# KMO_IO_MV2_7.net
KiCad netlist of a schematic drawn in EAGLE
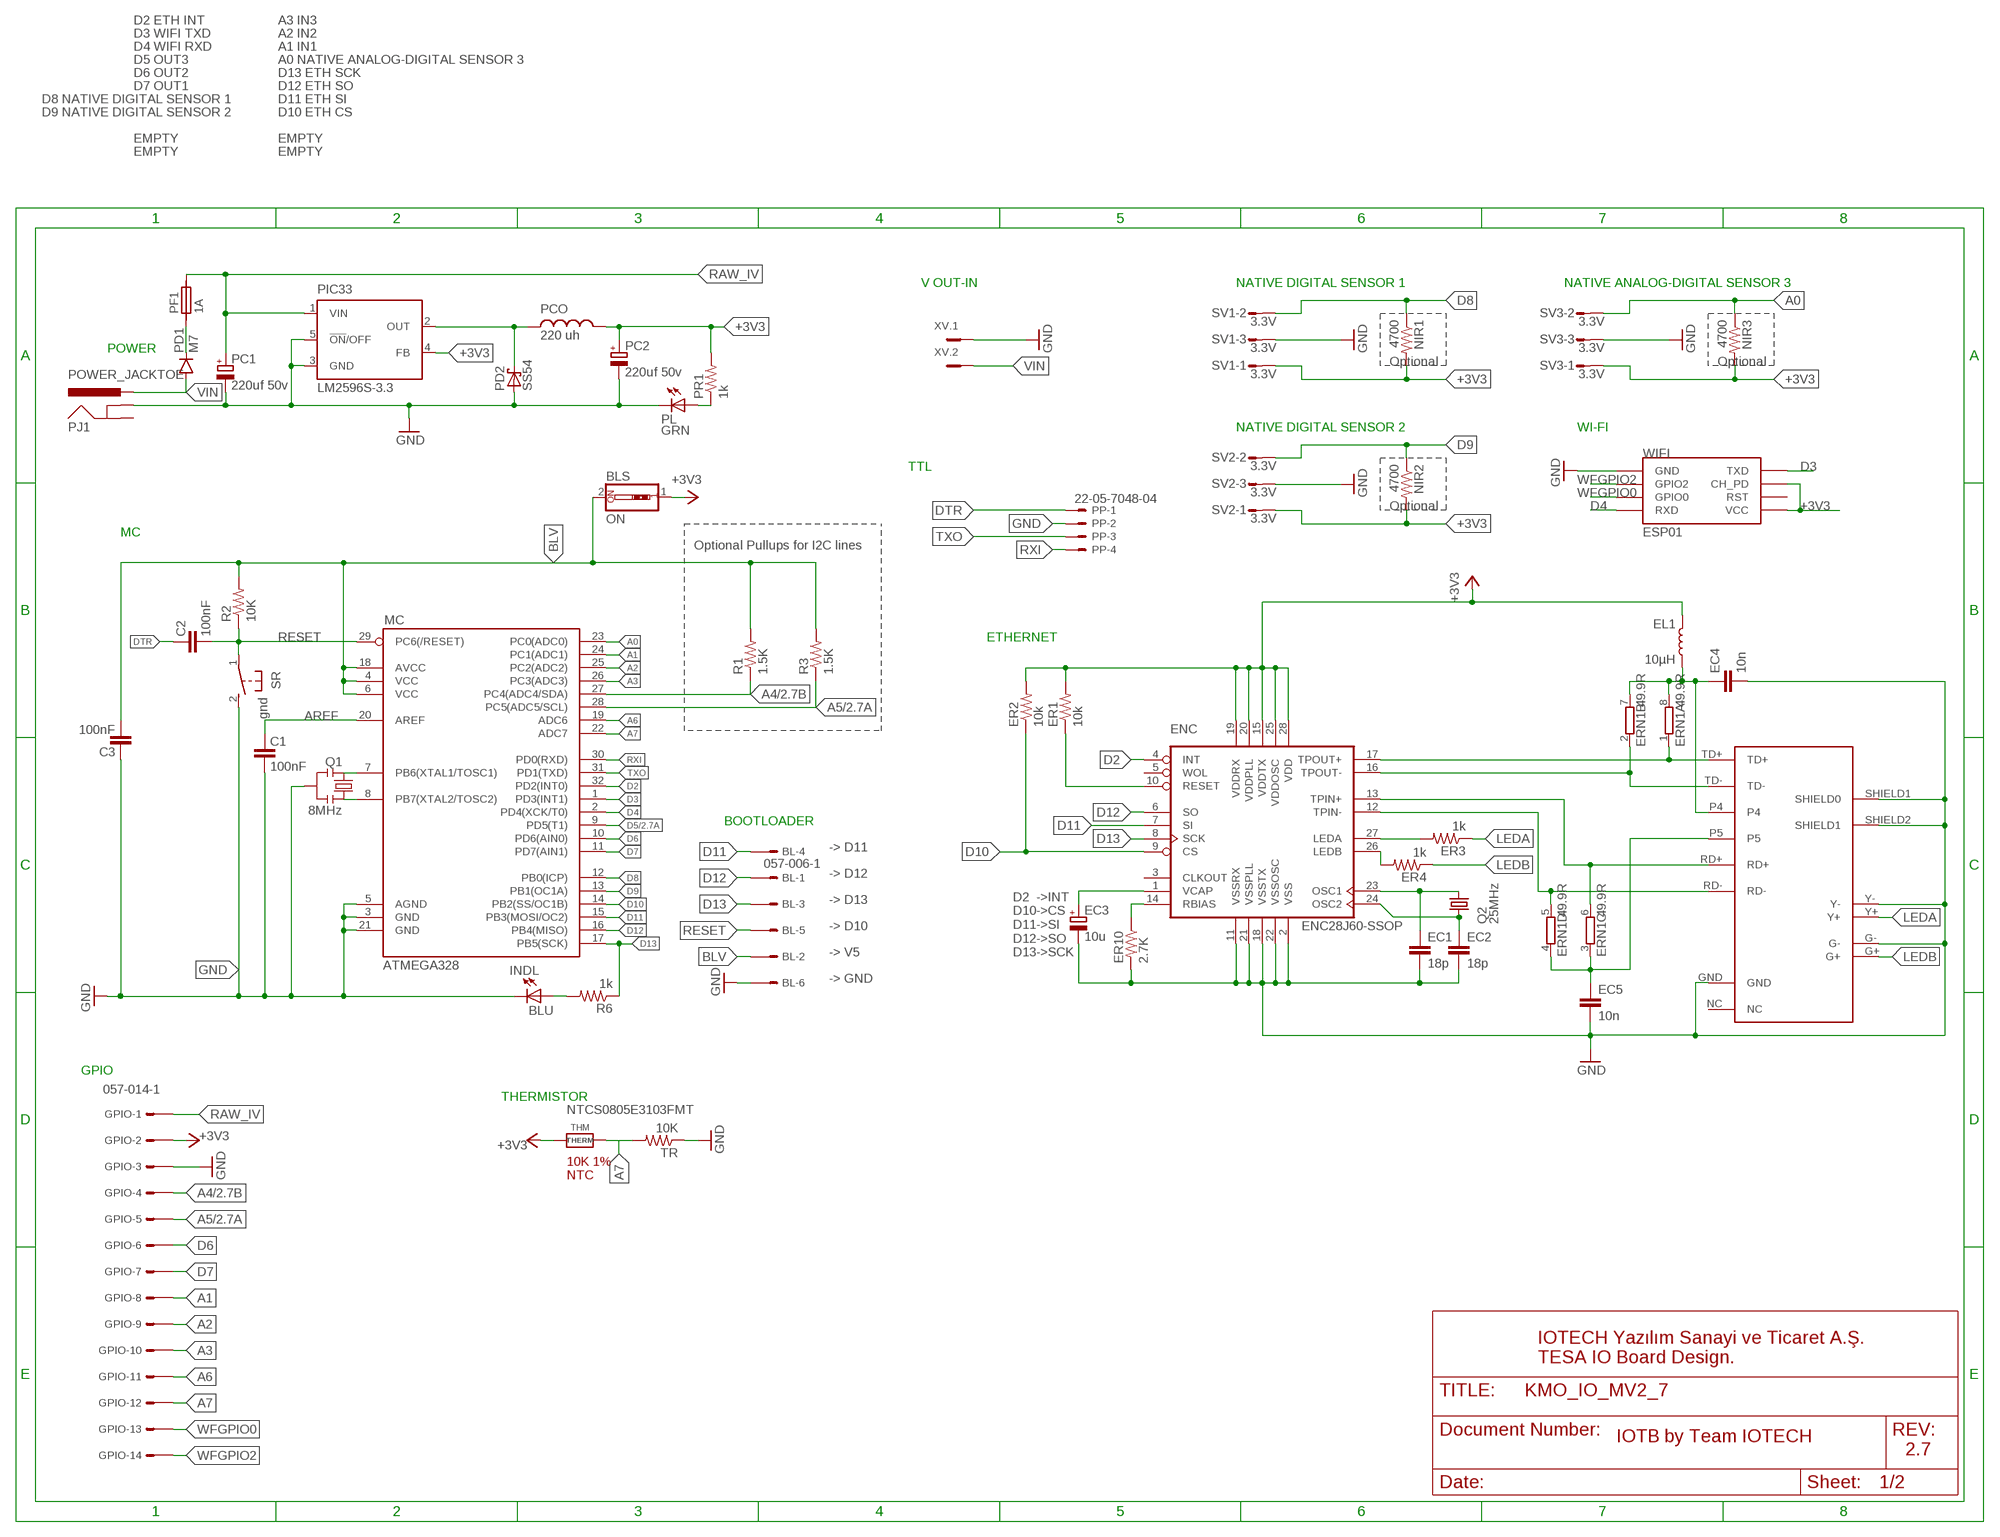
[diagram p0: schematic, sheet 1]
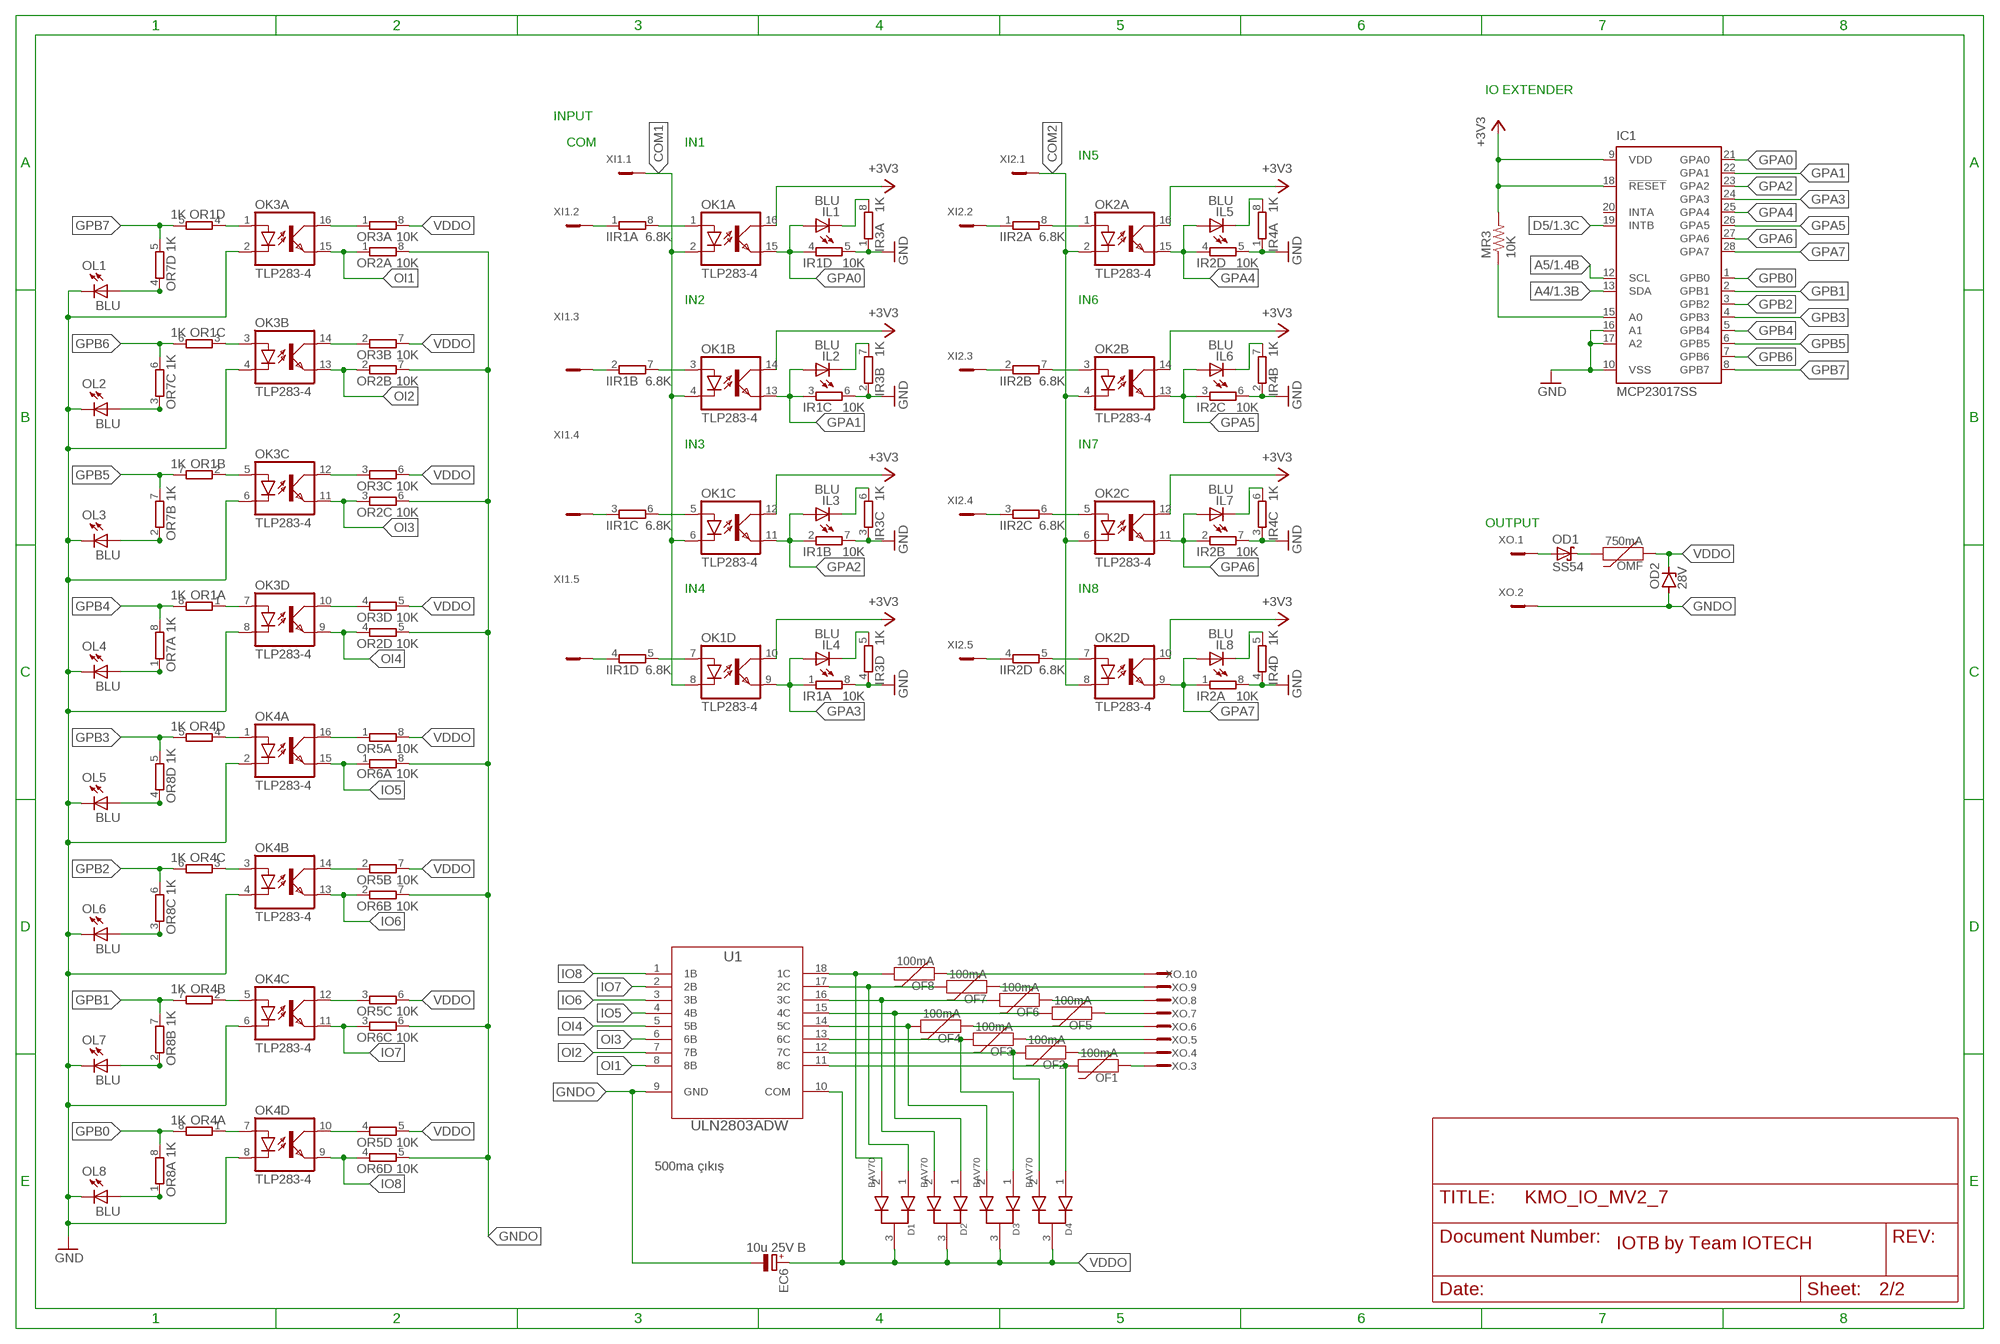
[diagram p1: schematic, sheet 2]

(export (version "E")
  (design (tool "Eeschema 10.0.6"))
  (components
    (comp (ref "BL")
      (value "057-006-1")
      (footprint "eagle-import:057-006-1")
      (libsource (lib "eagle-import") (part "057-006-1"))
    )
    (comp (ref "BLS")
      (value "ON")
      (footprint "eagle-import:EDG-01")
      (libsource (lib "eagle-import") (part "SW_DIP-1"))
    )
    (comp (ref "C1")
      (value "100nF")
      (footprint "eagle-import:0805")
      (libsource (lib "eagle-import") (part "CAP0805"))
    )
    (comp (ref "C2")
      (value "100nF")
      (footprint "eagle-import:0805")
      (libsource (lib "eagle-import") (part "CAP0805"))
    )
    (comp (ref "C3")
      (value "100nF")
      (footprint "eagle-import:0805")
      (libsource (lib "eagle-import") (part "CAP0805"))
    )
    (comp (ref "EC1")
      (value "18p")
      (footprint "eagle-import:0805")
      (libsource (lib "eagle-import") (part "CAP0805"))
    )
    (comp (ref "EC2")
      (value "18p")
      (footprint "eagle-import:0805")
      (libsource (lib "eagle-import") (part "CAP0805"))
    )
    (comp (ref "EC3")
      (value "10u")
      (footprint "eagle-import:CT3216")
      (libsource (lib "eagle-import") (part "CPOL-EUCT3216"))
    )
    (comp (ref "EC4")
      (value "10n")
      (footprint "eagle-import:0805")
      (libsource (lib "eagle-import") (part "CAP0805"))
    )
    (comp (ref "EC5")
      (value "10n")
      (footprint "eagle-import:0805")
      (libsource (lib "eagle-import") (part "CAP0805"))
    )
    (comp (ref "EL1")
      (value "10µH")
      (footprint "eagle-import:0805")
      (libsource (lib "eagle-import") (part "INDUCTOR-0805-3.3UH"))
    )
    (comp (ref "ENC")
      (value "ENC28J60-SSOP")
      (footprint "eagle-import:SSOP28")
      (libsource (lib "eagle-import") (part "ENC28J60-SSOP"))
    )
    (comp (ref "ER1")
      (value "10k")
      (footprint "eagle-import:0805")
      (libsource (lib "eagle-import") (part "RESISTOR0805-RES"))
    )
    (comp (ref "ER2")
      (value "10k")
      (footprint "eagle-import:0805")
      (libsource (lib "eagle-import") (part "RESISTOR0805-RES"))
    )
    (comp (ref "ER3")
      (value "1k")
      (footprint "eagle-import:0805")
      (libsource (lib "eagle-import") (part "RESISTOR0805-RES"))
    )
    (comp (ref "ER4")
      (value "1k")
      (footprint "eagle-import:0805")
      (libsource (lib "eagle-import") (part "RESISTOR0805-RES"))
    )
    (comp (ref "ER10")
      (value "2.7K")
      (footprint "eagle-import:0805")
      (libsource (lib "eagle-import") (part "RESISTOR0805-RES"))
    )
    (comp (ref "ERN1")
      (value "49.9R")
      (footprint "eagle-import:0603-ARV")
      (libsource (lib "eagle-import") (part "4R-N0603-ARV"))
    )
    (comp (ref "GPIO")
      (value "057-014-1")
      (footprint "eagle-import:057-014-1")
      (libsource (lib "eagle-import") (part "057-014-1"))
    )
    (comp (ref "INDL")
      (value "BLU")
      (footprint "eagle-import:CHIP-LED0805")
      (libsource (lib "eagle-import") (part "LEDCHIP-LED0805"))
    )
    (comp (ref "MC")
      (value "ATMEGA328")
      (footprint "eagle-import:TQFP32-08")
      (libsource (lib "eagle-import") (part "ATMEGA168"))
    )
    (comp (ref "NIR1")
      (value "4700")
      (footprint "eagle-import:0805")
      (libsource (lib "eagle-import") (part "RESISTOR0805-RES"))
    )
    (comp (ref "NIR2")
      (value "4700")
      (footprint "eagle-import:0805")
      (libsource (lib "eagle-import") (part "RESISTOR0805-RES"))
    )
    (comp (ref "NIR3")
      (value "4700")
      (footprint "eagle-import:0805")
      (libsource (lib "eagle-import") (part "RESISTOR0805-RES"))
    )
    (comp (ref "PC1")
      (value "220uf 50v")
      (footprint "eagle-import:140CLH-1010")
      (libsource (lib "eagle-import") (part "CPOL-EU140CLH-1010"))
    )
    (comp (ref "PC2")
      (value "220uf 50v")
      (footprint "eagle-import:140CLH-1010")
      (libsource (lib "eagle-import") (part "CPOL-EU140CLH-1010"))
    )
    (comp (ref "PCO")
      (value "220 uh")
      (footprint "eagle-import:MSS1260")
      (libsource (lib "eagle-import") (part "MSS1260"))
    )
    (comp (ref "PD1")
      (value "M7")
      (footprint "eagle-import:SMA-DIODE")
      (libsource (lib "eagle-import") (part "DIODESMA"))
    )
    (comp (ref "PD2")
      (value "SS54")
      (footprint "eagle-import:SMB")
      (libsource (lib "eagle-import") (part "SCHOTTKY-DIODESMD"))
    )
    (comp (ref "PF1")
      (value "1A")
      (footprint "eagle-import:1820")
      (libsource (lib "eagle-import") (part "SIBA194600"))
    )
    (comp (ref "PIC33")
      (value "LM2596S-3.3")
      (footprint "eagle-import:TO263-5")
      (fields
        (field (name "MF") "NATIONAL SEMICONDUCTOR")
        (field (name "MPN") "LM2596S-ADJ/NOPB")
        (field (name "SPICEPREFIX") "X")
      )
      (libsource (lib "eagle-import") (part "LM2596S"))
    )
    (comp (ref "PJ1")
      (value "POWER_JACKTOE")
      (footprint "eagle-import:POWER_JACK_SMD_OVERPASTE_TOE")
      (libsource (lib "eagle-import") (part "POWER_JACKTOE"))
    )
    (comp (ref "PL")
      (value "GRN")
      (footprint "eagle-import:CHIP-LED0805")
      (libsource (lib "eagle-import") (part "LEDCHIP-LED0805"))
    )
    (comp (ref "PP")
      (value "22-05-7048-04")
      (footprint "eagle-import:7395-04")
      (fields (field (name "MF") "MOLEX"))
      (libsource (lib "eagle-import") (part "22-?-0405-7048"))
    )
    (comp (ref "PR1")
      (value "1k")
      (footprint "eagle-import:0805")
      (libsource (lib "eagle-import") (part "RESISTOR0805-RES"))
    )
    (comp (ref "Q1")
      (value "8MHz")
      (footprint "eagle-import:RESONATOR-SMD-1_1")
      (libsource (lib "eagle-import") (part "RESONATOR1{colon}1"))
    )
    (comp (ref "Q2")
      (value "25MHz")
      (footprint "eagle-import:5.0X3.2_2")
      (libsource (lib "eagle-import") (part "KX-9B"))
    )
    (comp (ref "R1")
      (value "1.5K")
      (footprint "eagle-import:0805")
      (libsource (lib "eagle-import") (part "RESISTOR0805-RES"))
    )
    (comp (ref "R2")
      (value "10K")
      (footprint "eagle-import:0805")
      (libsource (lib "eagle-import") (part "RESISTOR0805-RES"))
    )
    (comp (ref "R3")
      (value "1.5K")
      (footprint "eagle-import:0805")
      (libsource (lib "eagle-import") (part "RESISTOR0805-RES"))
    )
    (comp (ref "R6")
      (value "1k")
      (footprint "eagle-import:0805")
      (libsource (lib "eagle-import") (part "RESISTOR0805-RES"))
    )
    (comp (ref "SR")
      (value "gnd")
      (footprint "eagle-import:B3F-31XX")
      (fields (field (name "MPN") "B3F-3100"))
      (libsource (lib "eagle-import") (part "31-XX"))
    )
    (comp (ref "SV1")
      (value "3.3V")
      (footprint "eagle-import:S03P")
      (libsource (lib "eagle-import") (part "S03P"))
    )
    (comp (ref "SV2")
      (value "3.3V")
      (footprint "eagle-import:S03P")
      (libsource (lib "eagle-import") (part "S03P"))
    )
    (comp (ref "SV3")
      (value "3.3V")
      (footprint "eagle-import:S03P")
      (libsource (lib "eagle-import") (part "S03P"))
    )
    (comp (ref "THM")
      (value "THERM")
      (footprint "eagle-import:MICROBUILDER_0805_NOTHERMALS")
      (libsource (lib "eagle-import") (part "MICROBUILDER_RESISTOR0805_NOTHERMALS"))
    )
    (comp (ref "TR")
      (value "10K")
      (footprint "eagle-import:0805")
      (libsource (lib "eagle-import") (part "RESISTOR0805-RES"))
    )
    (comp (ref "U$2")
      (value "HR911105A")
      (footprint "eagle-import:RJ45")
      (libsource (lib "eagle-import") (part "HR911105A"))
    )
    (comp (ref "WIFI")
      (value "ESP01")
      (footprint "eagle-import:ESP01")
      (libsource (lib "eagle-import") (part "ESP01"))
    )
    (comp (ref "XV")
      (value "MC2")
      (footprint "eagle-import:MC2")
      (libsource (lib "eagle-import") (part "MC2"))
    )
    (comp (ref "D1")
      (value "BAV70")
      (footprint "eagle-import:SOT-23-3")
      (fields (field (name "MF") "Multicomp") (field (name "MP") "BAV70+"))
      (libsource (lib "eagle-import") (part "BAV70"))
    )
    (comp (ref "D2")
      (value "BAV70")
      (footprint "eagle-import:SOT-23-3")
      (fields (field (name "MF") "Multicomp") (field (name "MP") "BAV70+"))
      (libsource (lib "eagle-import") (part "BAV70"))
    )
    (comp (ref "D3")
      (value "BAV70")
      (footprint "eagle-import:SOT-23-3")
      (fields (field (name "MF") "Multicomp") (field (name "MP") "BAV70+"))
      (libsource (lib "eagle-import") (part "BAV70"))
    )
    (comp (ref "D4")
      (value "BAV70")
      (footprint "eagle-import:SOT-23-3")
      (fields (field (name "MF") "Multicomp") (field (name "MP") "BAV70+"))
      (libsource (lib "eagle-import") (part "BAV70"))
    )
    (comp (ref "EC6")
      (value "10u 25V B")
      (footprint "eagle-import:SMC_B")
      (libsource (lib "eagle-import") (part "CPOL-EUSMCB"))
    )
    (comp (ref "IC1")
      (value "MCP23017SS")
      (footprint "eagle-import:SSOP28")
      (fields (field (name "MF") "MICROCHIP") (field (name "MPN") "MCP23017-E/SS"))
      (libsource (lib "eagle-import") (part "MCP23017SS"))
    )
    (comp (ref "IIR1")
      (value "6.8K")
      (footprint "eagle-import:0603-ARV")
      (libsource (lib "eagle-import") (part "4R-N0603-ARV"))
    )
    (comp (ref "IIR2")
      (value "6.8K")
      (footprint "eagle-import:0603-ARV")
      (libsource (lib "eagle-import") (part "4R-N0603-ARV"))
    )
    (comp (ref "IL1")
      (value "BLU")
      (footprint "eagle-import:CHIP-LED0805")
      (libsource (lib "eagle-import") (part "LEDCHIP-LED0805"))
    )
    (comp (ref "IL2")
      (value "BLU")
      (footprint "eagle-import:CHIP-LED0805")
      (libsource (lib "eagle-import") (part "LEDCHIP-LED0805"))
    )
    (comp (ref "IL3")
      (value "BLU")
      (footprint "eagle-import:CHIP-LED0805")
      (libsource (lib "eagle-import") (part "LEDCHIP-LED0805"))
    )
    (comp (ref "IL4")
      (value "BLU")
      (footprint "eagle-import:CHIP-LED0805")
      (libsource (lib "eagle-import") (part "LEDCHIP-LED0805"))
    )
    (comp (ref "IL5")
      (value "BLU")
      (footprint "eagle-import:CHIP-LED0805")
      (libsource (lib "eagle-import") (part "LEDCHIP-LED0805"))
    )
    (comp (ref "IL6")
      (value "BLU")
      (footprint "eagle-import:CHIP-LED0805")
      (libsource (lib "eagle-import") (part "LEDCHIP-LED0805"))
    )
    (comp (ref "IL7")
      (value "BLU")
      (footprint "eagle-import:CHIP-LED0805")
      (libsource (lib "eagle-import") (part "LEDCHIP-LED0805"))
    )
    (comp (ref "IL8")
      (value "BLU")
      (footprint "eagle-import:CHIP-LED0805")
      (libsource (lib "eagle-import") (part "LEDCHIP-LED0805"))
    )
    (comp (ref "IR1")
      (value "10K")
      (footprint "eagle-import:0603-ARV")
      (libsource (lib "eagle-import") (part "4R-N0603-ARV"))
    )
    (comp (ref "IR2")
      (value "10K")
      (footprint "eagle-import:0603-ARV")
      (libsource (lib "eagle-import") (part "4R-N0603-ARV"))
    )
    (comp (ref "IR3")
      (value "1K")
      (footprint "eagle-import:0603-ARV")
      (libsource (lib "eagle-import") (part "4R-N0603-ARV"))
    )
    (comp (ref "IR4")
      (value "1K")
      (footprint "eagle-import:0603-ARV")
      (libsource (lib "eagle-import") (part "4R-N0603-ARV"))
    )
    (comp (ref "MR3")
      (value "10K")
      (footprint "eagle-import:0805")
      (libsource (lib "eagle-import") (part "RESISTOR0805-RES"))
    )
    (comp (ref "OD1")
      (value "SS54")
      (footprint "eagle-import:SMB")
      (libsource (lib "eagle-import") (part "SCHOTTKY-DIODESMD"))
    )
    (comp (ref "OD2")
      (value "28V")
      (footprint "eagle-import:SMB")
      (libsource (lib "eagle-import") (part "ZENER-DIODESMB"))
    )
    (comp (ref "OF1")
      (value "100mA")
      (footprint "eagle-import:1206")
      (libsource (lib "eagle-import") (part "PPTC_0.75A"))
    )
    (comp (ref "OF2")
      (value "100mA")
      (footprint "eagle-import:1206")
      (libsource (lib "eagle-import") (part "PPTC_0.75A"))
    )
    (comp (ref "OF3")
      (value "100mA")
      (footprint "eagle-import:1206")
      (libsource (lib "eagle-import") (part "PPTC_0.75A"))
    )
    (comp (ref "OF4")
      (value "100mA")
      (footprint "eagle-import:1206")
      (libsource (lib "eagle-import") (part "PPTC_0.75A"))
    )
    (comp (ref "OF5")
      (value "100mA")
      (footprint "eagle-import:1206")
      (libsource (lib "eagle-import") (part "PPTC_0.75A"))
    )
    (comp (ref "OF6")
      (value "100mA")
      (footprint "eagle-import:1206")
      (libsource (lib "eagle-import") (part "PPTC_0.75A"))
    )
    (comp (ref "OF7")
      (value "100mA")
      (footprint "eagle-import:1206")
      (libsource (lib "eagle-import") (part "PPTC_0.75A"))
    )
    (comp (ref "OF8")
      (value "100mA")
      (footprint "eagle-import:1206")
      (libsource (lib "eagle-import") (part "PPTC_0.75A"))
    )
    (comp (ref "OK1")
      (value "TLP283-4")
      (footprint "eagle-import:MINI-FLAT-16")
      (fields (field (name "SPICEPREFIX") "O"))
      (libsource (lib "eagle-import") (part "TLP283-4"))
    )
    (comp (ref "OK2")
      (value "TLP283-4")
      (footprint "eagle-import:MINI-FLAT-16")
      (fields (field (name "SPICEPREFIX") "O"))
      (libsource (lib "eagle-import") (part "TLP283-4"))
    )
    (comp (ref "OK3")
      (value "TLP283-4")
      (footprint "eagle-import:MINI-FLAT-16")
      (libsource (lib "eagle-import") (part "TLP283-4"))
    )
    (comp (ref "OK4")
      (value "TLP283-4")
      (footprint "eagle-import:MINI-FLAT-16")
      (libsource (lib "eagle-import") (part "TLP283-4"))
    )
    (comp (ref "OL1")
      (value "BLU")
      (footprint "eagle-import:CHIP-LED0805")
      (libsource (lib "eagle-import") (part "LEDCHIP-LED0805"))
    )
    (comp (ref "OL2")
      (value "BLU")
      (footprint "eagle-import:CHIP-LED0805")
      (libsource (lib "eagle-import") (part "LEDCHIP-LED0805"))
    )
    (comp (ref "OL3")
      (value "BLU")
      (footprint "eagle-import:CHIP-LED0805")
      (libsource (lib "eagle-import") (part "LEDCHIP-LED0805"))
    )
    (comp (ref "OL4")
      (value "BLU")
      (footprint "eagle-import:CHIP-LED0805")
      (libsource (lib "eagle-import") (part "LEDCHIP-LED0805"))
    )
    (comp (ref "OL5")
      (value "BLU")
      (footprint "eagle-import:CHIP-LED0805")
      (libsource (lib "eagle-import") (part "LEDCHIP-LED0805"))
    )
    (comp (ref "OL6")
      (value "BLU")
      (footprint "eagle-import:CHIP-LED0805")
      (libsource (lib "eagle-import") (part "LEDCHIP-LED0805"))
    )
    (comp (ref "OL7")
      (value "BLU")
      (footprint "eagle-import:CHIP-LED0805")
      (libsource (lib "eagle-import") (part "LEDCHIP-LED0805"))
    )
    (comp (ref "OL8")
      (value "BLU")
      (footprint "eagle-import:CHIP-LED0805")
      (libsource (lib "eagle-import") (part "LEDCHIP-LED0805"))
    )
    (comp (ref "OMF")
      (value "750mA")
      (footprint "eagle-import:1206")
      (libsource (lib "eagle-import") (part "PPTC_0.75A"))
    )
    (comp (ref "OR1")
      (value "1K")
      (footprint "eagle-import:0603-ARV")
      (libsource (lib "eagle-import") (part "4R-N0603-ARV"))
    )
    (comp (ref "OR2")
      (value "10K")
      (footprint "eagle-import:0603-ARV")
      (libsource (lib "eagle-import") (part "4R-N0603-ARV"))
    )
    (comp (ref "OR3")
      (value "10K")
      (footprint "eagle-import:0603-ARV")
      (libsource (lib "eagle-import") (part "4R-N0603-ARV"))
    )
    (comp (ref "OR4")
      (value "1K")
      (footprint "eagle-import:0603-ARV")
      (libsource (lib "eagle-import") (part "4R-N0603-ARV"))
    )
    (comp (ref "OR5")
      (value "10K")
      (footprint "eagle-import:0603-ARV")
      (libsource (lib "eagle-import") (part "4R-N0603-ARV"))
    )
    (comp (ref "OR6")
      (value "10K")
      (footprint "eagle-import:0603-ARV")
      (libsource (lib "eagle-import") (part "4R-N0603-ARV"))
    )
    (comp (ref "OR7")
      (value "1K")
      (footprint "eagle-import:0603-ARV")
      (libsource (lib "eagle-import") (part "4R-N0603-ARV"))
    )
    (comp (ref "OR8")
      (value "1K")
      (footprint "eagle-import:0603-ARV")
      (libsource (lib "eagle-import") (part "4R-N0603-ARV"))
    )
    (comp (ref "U1")
      (value "ULN2803ADW")
      (footprint "eagle-import:SOIC127P1030X265-18N")
      (libsource (lib "eagle-import") (part "ULN2803ADW"))
    )
    (comp (ref "XI1")
      (value "MC5")
      (footprint "eagle-import:MC5")
      (libsource (lib "eagle-import") (part "MC5"))
    )
    (comp (ref "XI2")
      (value "MC5")
      (footprint "eagle-import:MC5")
      (libsource (lib "eagle-import") (part "MC5"))
    )
    (comp (ref "XO")
      (value "MC10")
      (footprint "eagle-import:MC10")
      (libsource (lib "eagle-import") (part "MC10"))
    )
  )
  (nets
    (net (code "1") (name "+3V3") (class "Default")
      (node (ref "BLS") (pin "1") (pinfunction "1_1") (pintype "passive"))
      (node (ref "EL1") (pin "1") (pinfunction "1_1") (pintype "passive"))
      (node (ref "ENC") (pin "15") (pinfunction "VDDTX_15") (pintype "power_in"))
      (node (ref "ENC") (pin "19") (pinfunction "VDDRX_19") (pintype "power_in"))
      (node (ref "ENC") (pin "20") (pinfunction "VDDPLL_20") (pintype "power_in"))
      (node (ref "ENC") (pin "25") (pinfunction "VDDOSC_25") (pintype "power_in"))
      (node (ref "ENC") (pin "28") (pinfunction "VDD_28") (pintype "power_in"))
      (node (ref "ER1") (pin "2") (pinfunction "2_2") (pintype "passive"))
      (node (ref "ER2") (pin "2") (pinfunction "2_2") (pintype "passive"))
      (node (ref "GPIO") (pin "2") (pinfunction "S_2") (pintype "passive"))
      (node (ref "IC1") (pin "18") (pinfunction "~{RESET}_18") (pintype "input"))
      (node (ref "IC1") (pin "9") (pinfunction "VDD_9") (pintype "power_in"))
      (node (ref "MR3") (pin "2") (pinfunction "2_2") (pintype "passive"))
      (node (ref "NIR1") (pin "2") (pinfunction "2_2") (pintype "passive"))
      (node (ref "NIR2") (pin "2") (pinfunction "2_2") (pintype "passive"))
      (node (ref "NIR3") (pin "2") (pinfunction "2_2") (pintype "passive"))
      (node (ref "OK1") (pin "10") (pinfunction "COL_10") (pintype "passive"))
      (node (ref "OK1") (pin "12") (pinfunction "COL_12") (pintype "passive"))
      (node (ref "OK1") (pin "14") (pinfunction "COL_14") (pintype "passive"))
      (node (ref "OK1") (pin "16") (pinfunction "COL_16") (pintype "passive"))
      (node (ref "OK2") (pin "10") (pinfunction "COL_10") (pintype "passive"))
      (node (ref "OK2") (pin "12") (pinfunction "COL_12") (pintype "passive"))
      (node (ref "OK2") (pin "14") (pinfunction "COL_14") (pintype "passive"))
      (node (ref "OK2") (pin "16") (pinfunction "COL_16") (pintype "passive"))
      (node (ref "PC2") (pin "+") (pinfunction "+_+") (pintype "passive"))
      (node (ref "PCO") (pin "P$1") (pinfunction "P$1_P$1") (pintype "passive"))
      (node (ref "PIC33") (pin "4") (pinfunction "FB_4") (pintype "input"))
      (node (ref "PR1") (pin "2") (pinfunction "2_2") (pintype "passive"))
      (node (ref "SV1") (pin "1") (pinfunction "S_1") (pintype "passive"))
      (node (ref "SV2") (pin "1") (pinfunction "S_1") (pintype "passive"))
      (node (ref "SV3") (pin "1") (pinfunction "S_1") (pintype "passive"))
      (node (ref "THM") (pin "1") (pinfunction "1_1") (pintype "passive"))
      (node (ref "WIFI") (pin "CH_PD") (pinfunction "CH_PD_CH_PD") (pintype "bidirectional"))
      (node (ref "WIFI") (pin "VCC") (pinfunction "VCC_VCC") (pintype "bidirectional"))
    )
    (net (code "2") (name "A0") (class "Default")
      (node (ref "MC") (pin "23") (pinfunction "PC0(ADC0)_23") (pintype "bidirectional"))
      (node (ref "NIR3") (pin "1") (pinfunction "1_1") (pintype "passive"))
      (node (ref "SV3") (pin "2") (pinfunction "S_2") (pintype "passive"))
    )
    (net (code "3") (name "A1") (class "Default")
      (node (ref "GPIO") (pin "8") (pinfunction "S_8") (pintype "passive"))
      (node (ref "MC") (pin "24") (pinfunction "PC1(ADC1)_24") (pintype "bidirectional"))
    )
    (net (code "4") (name "A2") (class "Default")
      (node (ref "GPIO") (pin "9") (pinfunction "S_9") (pintype "passive"))
      (node (ref "MC") (pin "25") (pinfunction "PC2(ADC2)_25") (pintype "bidirectional"))
    )
    (net (code "5") (name "A3") (class "Default")
      (node (ref "GPIO") (pin "10") (pinfunction "S_10") (pintype "passive"))
      (node (ref "MC") (pin "26") (pinfunction "PC3(ADC3)_26") (pintype "bidirectional"))
    )
    (net (code "6") (name "A4") (class "Default")
      (node (ref "GPIO") (pin "4") (pinfunction "S_4") (pintype "passive"))
      (node (ref "IC1") (pin "13") (pinfunction "SDA_13") (pintype "bidirectional"))
      (node (ref "MC") (pin "27") (pinfunction "PC4(ADC4/SDA)_27") (pintype "bidirectional"))
      (node (ref "R1") (pin "1") (pinfunction "1_1") (pintype "passive"))
    )
    (net (code "7") (name "A5") (class "Default")
      (node (ref "GPIO") (pin "5") (pinfunction "S_5") (pintype "passive"))
      (node (ref "IC1") (pin "12") (pinfunction "SCL_12") (pintype "input"))
      (node (ref "MC") (pin "28") (pinfunction "PC5(ADC5/SCL)_28") (pintype "bidirectional"))
      (node (ref "R3") (pin "1") (pinfunction "1_1") (pintype "passive"))
    )
    (net (code "8") (name "A6") (class "Default")
      (node (ref "GPIO") (pin "11") (pinfunction "S_11") (pintype "passive"))
      (node (ref "MC") (pin "19") (pinfunction "ADC6_19") (pintype "bidirectional"))
    )
    (net (code "9") (name "A7") (class "Default")
      (node (ref "GPIO") (pin "12") (pinfunction "S_12") (pintype "passive"))
      (node (ref "MC") (pin "22") (pinfunction "ADC7_22") (pintype "bidirectional"))
      (node (ref "THM") (pin "2") (pinfunction "2_2") (pintype "passive"))
      (node (ref "TR") (pin "2") (pinfunction "2_2") (pintype "passive"))
    )
    (net (code "10") (name "AREF") (class "Default")
      (node (ref "C1") (pin "2") (pinfunction "2_2") (pintype "passive"))
      (node (ref "MC") (pin "20") (pinfunction "AREF_20") (pintype "bidirectional"))
    )
    (net (code "11") (name "BLV") (class "Default")
      (node (ref "BL") (pin "2") (pinfunction "S_2") (pintype "passive"))
      (node (ref "BLS") (pin "2") (pinfunction "2_2") (pintype "passive"))
      (node (ref "C3") (pin "1") (pinfunction "1_1") (pintype "passive"))
      (node (ref "MC") (pin "18") (pinfunction "AVCC_18") (pintype "bidirectional"))
      (node (ref "MC") (pin "4") (pinfunction "VCC_4") (pintype "bidirectional"))
      (node (ref "MC") (pin "6") (pinfunction "VCC_6") (pintype "bidirectional"))
      (node (ref "R1") (pin "2") (pinfunction "2_2") (pintype "passive"))
      (node (ref "R2") (pin "2") (pinfunction "2_2") (pintype "passive"))
      (node (ref "R3") (pin "2") (pinfunction "2_2") (pintype "passive"))
    )
    (net (code "12") (name "COM1") (class "Default")
      (node (ref "OK1") (pin "2") (pinfunction "C_2") (pintype "passive"))
      (node (ref "OK1") (pin "4") (pinfunction "C_4") (pintype "passive"))
      (node (ref "OK1") (pin "6") (pinfunction "C_6") (pintype "passive"))
      (node (ref "OK1") (pin "8") (pinfunction "C_8") (pintype "passive"))
      (node (ref "XI1") (pin "1") (pinfunction "SK_1") (pintype "passive"))
    )
    (net (code "13") (name "COM2") (class "Default")
      (node (ref "OK2") (pin "2") (pinfunction "C_2") (pintype "passive"))
      (node (ref "OK2") (pin "4") (pinfunction "C_4") (pintype "passive"))
      (node (ref "OK2") (pin "6") (pinfunction "C_6") (pintype "passive"))
      (node (ref "OK2") (pin "8") (pinfunction "C_8") (pintype "passive"))
      (node (ref "XI2") (pin "1") (pinfunction "SK_1") (pintype "passive"))
    )
    (net (code "14") (name "D2") (class "Default")
      (node (ref "ENC") (pin "4") (pinfunction "INT_4") (pintype "output"))
      (node (ref "MC") (pin "32") (pinfunction "PD2(INT0)_32") (pintype "bidirectional"))
    )
    (net (code "15") (name "D3") (class "Default")
      (node (ref "MC") (pin "1") (pinfunction "PD3(INT1)_1") (pintype "bidirectional"))
      (node (ref "WIFI") (pin "TX") (pinfunction "TXD_TX") (pintype "bidirectional"))
    )
    (net (code "16") (name "D4") (class "Default")
      (node (ref "MC") (pin "2") (pinfunction "PD4(XCK/T0)_2") (pintype "bidirectional"))
      (node (ref "WIFI") (pin "RX") (pinfunction "RXD_RX") (pintype "bidirectional"))
    )
    (net (code "17") (name "D5") (class "Default")
      (node (ref "IC1") (pin "19") (pinfunction "INTB_19") (pintype "output"))
      (node (ref "MC") (pin "9") (pinfunction "PD5(T1)_9") (pintype "bidirectional"))
    )
    (net (code "18") (name "D6") (class "Default")
      (node (ref "GPIO") (pin "6") (pinfunction "S_6") (pintype "passive"))
      (node (ref "MC") (pin "10") (pinfunction "PD6(AIN0)_10") (pintype "bidirectional"))
    )
    (net (code "19") (name "D7") (class "Default")
      (node (ref "GPIO") (pin "7") (pinfunction "S_7") (pintype "passive"))
      (node (ref "MC") (pin "11") (pinfunction "PD7(AIN1)_11") (pintype "bidirectional"))
    )
    (net (code "20") (name "D8") (class "Default")
      (node (ref "MC") (pin "12") (pinfunction "PB0(ICP)_12") (pintype "bidirectional"))
      (node (ref "NIR1") (pin "1") (pinfunction "1_1") (pintype "passive"))
      (node (ref "SV1") (pin "2") (pinfunction "S_2") (pintype "passive"))
    )
    (net (code "21") (name "D9") (class "Default")
      (node (ref "MC") (pin "13") (pinfunction "PB1(OC1A)_13") (pintype "bidirectional"))
      (node (ref "NIR2") (pin "1") (pinfunction "1_1") (pintype "passive"))
      (node (ref "SV2") (pin "2") (pinfunction "S_2") (pintype "passive"))
    )
    (net (code "22") (name "D10") (class "Default")
      (node (ref "ENC") (pin "9") (pinfunction "CS_9") (pintype "input"))
      (node (ref "ER2") (pin "1") (pinfunction "1_1") (pintype "passive"))
      (node (ref "MC") (pin "14") (pinfunction "PB2(SS/OC1B)_14") (pintype "bidirectional"))
    )
    (net (code "23") (name "D11") (class "Default")
      (node (ref "BL") (pin "4") (pinfunction "S_4") (pintype "passive"))
      (node (ref "ENC") (pin "7") (pinfunction "SI_7") (pintype "input"))
      (node (ref "MC") (pin "15") (pinfunction "PB3(MOSI/OC2)_15") (pintype "bidirectional"))
    )
    (net (code "24") (name "D12") (class "Default")
      (node (ref "BL") (pin "1") (pinfunction "S_1") (pintype "passive"))
      (node (ref "ENC") (pin "6") (pinfunction "SO_6") (pintype "output"))
      (node (ref "MC") (pin "16") (pinfunction "PB4(MISO)_16") (pintype "bidirectional"))
    )
    (net (code "25") (name "D13") (class "Default")
      (node (ref "BL") (pin "3") (pinfunction "S_3") (pintype "passive"))
      (node (ref "ENC") (pin "8") (pinfunction "SCK_8") (pintype "input"))
      (node (ref "MC") (pin "17") (pinfunction "PB5(SCK)_17") (pintype "bidirectional"))
      (node (ref "R6") (pin "1") (pinfunction "1_1") (pintype "passive"))
    )
    (net (code "26") (name "DTR") (class "Default")
      (node (ref "C2") (pin "2") (pinfunction "2_2") (pintype "passive"))
      (node (ref "PP") (pin "1") (pinfunction "S_1") (pintype "passive"))
    )
    (net (code "27") (name "GND") (class "Default")
      (node (ref "BL") (pin "6") (pinfunction "S_6") (pintype "passive"))
      (node (ref "C1") (pin "1") (pinfunction "1_1") (pintype "passive"))
      (node (ref "C3") (pin "2") (pinfunction "2_2") (pintype "passive"))
      (node (ref "EC1") (pin "2") (pinfunction "2_2") (pintype "passive"))
      (node (ref "EC2") (pin "2") (pinfunction "2_2") (pintype "passive"))
      (node (ref "EC3") (pin "-") (pinfunction "-_-") (pintype "passive"))
      (node (ref "EC4") (pin "2") (pinfunction "2_2") (pintype "passive"))
      (node (ref "EC5") (pin "2") (pinfunction "2_2") (pintype "passive"))
      (node (ref "ENC") (pin "11") (pinfunction "VSSRX_11") (pintype "power_in"))
      (node (ref "ENC") (pin "18") (pinfunction "VSSTX_18") (pintype "power_in"))
      (node (ref "ENC") (pin "2") (pinfunction "VSS_2") (pintype "power_in"))
      (node (ref "ENC") (pin "21") (pinfunction "VSSPLL_21") (pintype "power_in"))
      (node (ref "ENC") (pin "22") (pinfunction "VSSOSC_22") (pintype "power_in"))
      (node (ref "ER10") (pin "2") (pinfunction "2_2") (pintype "passive"))
      (node (ref "GPIO") (pin "3") (pinfunction "S_3") (pintype "passive"))
      (node (ref "IC1") (pin "10") (pinfunction "VSS_10") (pintype "power_in"))
      (node (ref "IC1") (pin "16") (pinfunction "A1_16") (pintype "input"))
      (node (ref "IC1") (pin "17") (pinfunction "A2_17") (pintype "input"))
      (node (ref "INDL") (pin "C") (pinfunction "C_C") (pintype "passive"))
      (node (ref "IR1") (pin "5") (pinfunction "2_5") (pintype "passive"))
      (node (ref "IR1") (pin "6") (pinfunction "2_6") (pintype "passive"))
      (node (ref "IR1") (pin "7") (pinfunction "2_7") (pintype "passive"))
      (node (ref "IR1") (pin "8") (pinfunction "2_8") (pintype "passive"))
      (node (ref "IR2") (pin "5") (pinfunction "2_5") (pintype "passive"))
      (node (ref "IR2") (pin "6") (pinfunction "2_6") (pintype "passive"))
      (node (ref "IR2") (pin "7") (pinfunction "2_7") (pintype "passive"))
      (node (ref "IR2") (pin "8") (pinfunction "2_8") (pintype "passive"))
      (node (ref "IR3") (pin "1") (pinfunction "1_1") (pintype "passive"))
      (node (ref "IR3") (pin "2") (pinfunction "1_2") (pintype "passive"))
      (node (ref "IR3") (pin "3") (pinfunction "1_3") (pintype "passive"))
      (node (ref "IR3") (pin "4") (pinfunction "1_4") (pintype "passive"))
      (node (ref "IR4") (pin "1") (pinfunction "1_1") (pintype "passive"))
      (node (ref "IR4") (pin "2") (pinfunction "1_2") (pintype "passive"))
      (node (ref "IR4") (pin "3") (pinfunction "1_3") (pintype "passive"))
      (node (ref "IR4") (pin "4") (pinfunction "1_4") (pintype "passive"))
      (node (ref "MC") (pin "21") (pinfunction "GND_21") (pintype "bidirectional"))
      (node (ref "MC") (pin "3") (pinfunction "GND_3") (pintype "bidirectional"))
      (node (ref "MC") (pin "5") (pinfunction "AGND_5") (pintype "bidirectional"))
      (node (ref "OK3") (pin "2") (pinfunction "C_2") (pintype "passive"))
      (node (ref "OK3") (pin "4") (pinfunction "C_4") (pintype "passive"))
      (node (ref "OK3") (pin "6") (pinfunction "C_6") (pintype "passive"))
      (node (ref "OK3") (pin "8") (pinfunction "C_8") (pintype "passive"))
      (node (ref "OK4") (pin "2") (pinfunction "C_2") (pintype "passive"))
      (node (ref "OK4") (pin "4") (pinfunction "C_4") (pintype "passive"))
      (node (ref "OK4") (pin "6") (pinfunction "C_6") (pintype "passive"))
      (node (ref "OK4") (pin "8") (pinfunction "C_8") (pintype "passive"))
      (node (ref "OL1") (pin "C") (pinfunction "C_C") (pintype "passive"))
      (node (ref "OL2") (pin "C") (pinfunction "C_C") (pintype "passive"))
      (node (ref "OL3") (pin "C") (pinfunction "C_C") (pintype "passive"))
      (node (ref "OL4") (pin "C") (pinfunction "C_C") (pintype "passive"))
      (node (ref "OL5") (pin "C") (pinfunction "C_C") (pintype "passive"))
      (node (ref "OL6") (pin "C") (pinfunction "C_C") (pintype "passive"))
      (node (ref "OL7") (pin "C") (pinfunction "C_C") (pintype "passive"))
      (node (ref "OL8") (pin "C") (pinfunction "C_C") (pintype "passive"))
      (node (ref "PC1") (pin "-") (pinfunction "-_-") (pintype "passive"))
      (node (ref "PC2") (pin "-") (pinfunction "-_-") (pintype "passive"))
      (node (ref "PD2") (pin "A") (pinfunction "A_A") (pintype "passive"))
      (node (ref "PIC33") (pin "3") (pinfunction "GND_3") (pintype "power_in"))
      (node (ref "PIC33") (pin "5") (pinfunction "~{ON}/OFF_5") (pintype "input"))
      (node (ref "PJ1") (pin "GND") (pinfunction "GNDBREAK_GND") (pintype "bidirectional"))
      (node (ref "PL") (pin "C") (pinfunction "C_C") (pintype "passive"))
      (node (ref "PP") (pin "2") (pinfunction "S_2") (pintype "passive"))
      (node (ref "Q1") (pin "2") (pinfunction "2_2") (pintype "passive"))
      (node (ref "SR") (pin "2") (pinfunction "S_2") (pintype "passive"))
      (node (ref "SV1") (pin "3") (pinfunction "S_3") (pintype "passive"))
      (node (ref "SV2") (pin "3") (pinfunction "S_3") (pintype "passive"))
      (node (ref "SV3") (pin "3") (pinfunction "S_3") (pintype "passive"))
      (node (ref "TR") (pin "1") (pinfunction "1_1") (pintype "passive"))
      (node (ref "U$2") (pin "G-") (pinfunction "G-_G-") (pintype "bidirectional"))
      (node (ref "U$2") (pin "GND") (pinfunction "GND_GND") (pintype "bidirectional"))
      (node (ref "U$2") (pin "SHIELD1") (pinfunction "SHIELD0_SHIELD1") (pintype "bidirectional"))
      (node (ref "U$2") (pin "SHIELD2") (pinfunction "SHIELD1_SHIELD2") (pintype "bidirectional"))
      (node (ref "U$2") (pin "Y-") (pinfunction "Y-_Y-") (pintype "bidirectional"))
      (node (ref "WIFI") (pin "GND") (pinfunction "GND_GND") (pintype "bidirectional"))
      (node (ref "XV") (pin "1") (pinfunction "SK_1") (pintype "passive"))
    )
    (net (code "28") (name "GNDO") (class "Default")
      (node (ref "EC6") (pin "-") (pinfunction "-_-") (pintype "passive"))
      (node (ref "OD2") (pin "A") (pinfunction "A_A") (pintype "passive"))
      (node (ref "OR2") (pin "5") (pinfunction "2_5") (pintype "passive"))
      (node (ref "OR2") (pin "6") (pinfunction "2_6") (pintype "passive"))
      (node (ref "OR2") (pin "7") (pinfunction "2_7") (pintype "passive"))
      (node (ref "OR2") (pin "8") (pinfunction "2_8") (pintype "passive"))
      (node (ref "OR6") (pin "5") (pinfunction "2_5") (pintype "passive"))
      (node (ref "OR6") (pin "6") (pinfunction "2_6") (pintype "passive"))
      (node (ref "OR6") (pin "7") (pinfunction "2_7") (pintype "passive"))
      (node (ref "OR6") (pin "8") (pinfunction "2_8") (pintype "passive"))
      (node (ref "U1") (pin "9") (pinfunction "GND_9") (pintype "passive"))
      (node (ref "XO") (pin "2") (pinfunction "SK_2") (pintype "passive"))
    )
    (net (code "29") (name "GPA0") (class "Default")
      (node (ref "IC1") (pin "21") (pinfunction "GPA0_21") (pintype "bidirectional"))
      (node (ref "IL1") (pin "A") (pinfunction "A_A") (pintype "passive"))
      (node (ref "IR1") (pin "4") (pinfunction "1_4") (pintype "passive"))
      (node (ref "OK1") (pin "15") (pinfunction "EMIT_15") (pintype "passive"))
    )
    (net (code "30") (name "GPA1") (class "Default")
      (node (ref "IC1") (pin "22") (pinfunction "GPA1_22") (pintype "bidirectional"))
      (node (ref "IL2") (pin "A") (pinfunction "A_A") (pintype "passive"))
      (node (ref "IR1") (pin "3") (pinfunction "1_3") (pintype "passive"))
      (node (ref "OK1") (pin "13") (pinfunction "EMIT_13") (pintype "passive"))
    )
    (net (code "31") (name "GPA2") (class "Default")
      (node (ref "IC1") (pin "23") (pinfunction "GPA2_23") (pintype "bidirectional"))
      (node (ref "IL3") (pin "A") (pinfunction "A_A") (pintype "passive"))
      (node (ref "IR1") (pin "2") (pinfunction "1_2") (pintype "passive"))
      (node (ref "OK1") (pin "11") (pinfunction "EMIT_11") (pintype "passive"))
    )
    (net (code "32") (name "GPA3") (class "Default")
      (node (ref "IC1") (pin "24") (pinfunction "GPA3_24") (pintype "bidirectional"))
      (node (ref "IL4") (pin "A") (pinfunction "A_A") (pintype "passive"))
      (node (ref "IR1") (pin "1") (pinfunction "1_1") (pintype "passive"))
      (node (ref "OK1") (pin "9") (pinfunction "EMIT_9") (pintype "passive"))
    )
    (net (code "33") (name "GPA4") (class "Default")
      (node (ref "IC1") (pin "25") (pinfunction "GPA4_25") (pintype "bidirectional"))
      (node (ref "IL5") (pin "A") (pinfunction "A_A") (pintype "passive"))
      (node (ref "IR2") (pin "4") (pinfunction "1_4") (pintype "passive"))
      (node (ref "OK2") (pin "15") (pinfunction "EMIT_15") (pintype "passive"))
    )
    (net (code "34") (name "GPA5") (class "Default")
      (node (ref "IC1") (pin "26") (pinfunction "GPA5_26") (pintype "bidirectional"))
      (node (ref "IL6") (pin "A") (pinfunction "A_A") (pintype "passive"))
      (node (ref "IR2") (pin "3") (pinfunction "1_3") (pintype "passive"))
      (node (ref "OK2") (pin "13") (pinfunction "EMIT_13") (pintype "passive"))
    )
    (net (code "35") (name "GPA6") (class "Default")
      (node (ref "IC1") (pin "27") (pinfunction "GPA6_27") (pintype "bidirectional"))
      (node (ref "IL7") (pin "A") (pinfunction "A_A") (pintype "passive"))
      (node (ref "IR2") (pin "2") (pinfunction "1_2") (pintype "passive"))
      (node (ref "OK2") (pin "11") (pinfunction "EMIT_11") (pintype "passive"))
    )
    (net (code "36") (name "GPA7") (class "Default")
      (node (ref "IC1") (pin "28") (pinfunction "GPA7_28") (pintype "bidirectional"))
      (node (ref "IL8") (pin "A") (pinfunction "A_A") (pintype "passive"))
      (node (ref "IR2") (pin "1") (pinfunction "1_1") (pintype "passive"))
      (node (ref "OK2") (pin "9") (pinfunction "EMIT_9") (pintype "passive"))
    )
    (net (code "37") (name "GPB0") (class "Default")
      (node (ref "IC1") (pin "1") (pinfunction "GPB0_1") (pintype "bidirectional"))
      (node (ref "OR4") (pin "8") (pinfunction "2_8") (pintype "passive"))
      (node (ref "OR8") (pin "8") (pinfunction "2_8") (pintype "passive"))
    )
    (net (code "38") (name "GPB1") (class "Default")
      (node (ref "IC1") (pin "2") (pinfunction "GPB1_2") (pintype "bidirectional"))
      (node (ref "OR4") (pin "7") (pinfunction "2_7") (pintype "passive"))
      (node (ref "OR8") (pin "7") (pinfunction "2_7") (pintype "passive"))
    )
    (net (code "39") (name "GPB2") (class "Default")
      (node (ref "IC1") (pin "3") (pinfunction "GPB2_3") (pintype "bidirectional"))
      (node (ref "OR4") (pin "6") (pinfunction "2_6") (pintype "passive"))
      (node (ref "OR8") (pin "6") (pinfunction "2_6") (pintype "passive"))
    )
    (net (code "40") (name "GPB3") (class "Default")
      (node (ref "IC1") (pin "4") (pinfunction "GPB3_4") (pintype "bidirectional"))
      (node (ref "OR4") (pin "5") (pinfunction "2_5") (pintype "passive"))
      (node (ref "OR8") (pin "5") (pinfunction "2_5") (pintype "passive"))
    )
    (net (code "41") (name "GPB4") (class "Default")
      (node (ref "IC1") (pin "5") (pinfunction "GPB4_5") (pintype "bidirectional"))
      (node (ref "OR1") (pin "8") (pinfunction "2_8") (pintype "passive"))
      (node (ref "OR7") (pin "8") (pinfunction "2_8") (pintype "passive"))
    )
    (net (code "42") (name "GPB5") (class "Default")
      (node (ref "IC1") (pin "6") (pinfunction "GPB5_6") (pintype "bidirectional"))
      (node (ref "OR1") (pin "7") (pinfunction "2_7") (pintype "passive"))
      (node (ref "OR7") (pin "7") (pinfunction "2_7") (pintype "passive"))
    )
    (net (code "43") (name "GPB6") (class "Default")
      (node (ref "IC1") (pin "7") (pinfunction "GPB6_7") (pintype "bidirectional"))
      (node (ref "OR1") (pin "6") (pinfunction "2_6") (pintype "passive"))
      (node (ref "OR7") (pin "6") (pinfunction "2_6") (pintype "passive"))
    )
    (net (code "44") (name "GPB7") (class "Default")
      (node (ref "IC1") (pin "8") (pinfunction "GPB7_8") (pintype "bidirectional"))
      (node (ref "OR1") (pin "5") (pinfunction "2_5") (pintype "passive"))
      (node (ref "OR7") (pin "5") (pinfunction "2_5") (pintype "passive"))
    )
    (net (code "45") (name "IO5") (class "Default")
      (node (ref "OK4") (pin "15") (pinfunction "EMIT_15") (pintype "passive"))
      (node (ref "OR6") (pin "1") (pinfunction "1_1") (pintype "passive"))
      (node (ref "U1") (pin "4") (pinfunction "4B_4") (pintype "input"))
    )
    (net (code "46") (name "IO6") (class "Default")
      (node (ref "OK4") (pin "13") (pinfunction "EMIT_13") (pintype "passive"))
      (node (ref "OR6") (pin "2") (pinfunction "1_2") (pintype "passive"))
      (node (ref "U1") (pin "3") (pinfunction "3B_3") (pintype "input"))
    )
    (net (code "47") (name "IO7") (class "Default")
      (node (ref "OK4") (pin "11") (pinfunction "EMIT_11") (pintype "passive"))
      (node (ref "OR6") (pin "3") (pinfunction "1_3") (pintype "passive"))
      (node (ref "U1") (pin "2") (pinfunction "2B_2") (pintype "input"))
    )
    (net (code "48") (name "IO8") (class "Default")
      (node (ref "OK4") (pin "9") (pinfunction "EMIT_9") (pintype "passive"))
      (node (ref "OR6") (pin "4") (pinfunction "1_4") (pintype "passive"))
      (node (ref "U1") (pin "1") (pinfunction "1B_1") (pintype "input"))
    )
    (net (code "49") (name "LEDA") (class "Default")
      (node (ref "ER3") (pin "1") (pinfunction "1_1") (pintype "passive"))
      (node (ref "U$2") (pin "Y+") (pinfunction "Y+_Y+") (pintype "bidirectional"))
    )
    (net (code "50") (name "LEDB") (class "Default")
      (node (ref "ER4") (pin "1") (pinfunction "1_1") (pintype "passive"))
      (node (ref "U$2") (pin "G+") (pinfunction "G+_G+") (pintype "bidirectional"))
    )
    (net (code "51") (name "Net-(ENC-LEDA)") (class "Default")
      (node (ref "ENC") (pin "27") (pinfunction "LEDA_27") (pintype "output"))
      (node (ref "ER3") (pin "2") (pinfunction "2_2") (pintype "passive"))
    )
    (net (code "52") (name "Net-(ENC-LEDB)") (class "Default")
      (node (ref "ENC") (pin "26") (pinfunction "LEDB_26") (pintype "output"))
      (node (ref "ER4") (pin "2") (pinfunction "2_2") (pintype "passive"))
    )
    (net (code "53") (name "Net-(ENC-OSC1)") (class "Default")
      (node (ref "EC1") (pin "1") (pinfunction "1_1") (pintype "passive"))
      (node (ref "ENC") (pin "23") (pinfunction "OSC1_23") (pintype "input"))
      (node (ref "Q2") (pin "2") (pinfunction "2_2") (pintype "passive"))
    )
    (net (code "54") (name "Net-(ENC-OSC2)") (class "Default")
      (node (ref "EC2") (pin "1") (pinfunction "1_1") (pintype "passive"))
      (node (ref "ENC") (pin "24") (pinfunction "OSC2_24") (pintype "output"))
      (node (ref "Q2") (pin "1") (pinfunction "1_1") (pintype "passive"))
    )
    (net (code "55") (name "Net-(ENC-RBIAS)") (class "Default")
      (node (ref "ENC") (pin "14") (pinfunction "RBIAS_14") (pintype "passive"))
      (node (ref "ER10") (pin "1") (pinfunction "1_1") (pintype "passive"))
    )
    (net (code "56") (name "Net-(ENC-RESET)") (class "Default")
      (node (ref "ENC") (pin "10") (pinfunction "RESET_10") (pintype "input"))
      (node (ref "ER1") (pin "1") (pinfunction "1_1") (pintype "passive"))
    )
    (net (code "57") (name "Net-(ENC-TPIN+)") (class "Default")
      (node (ref "ENC") (pin "13") (pinfunction "TPIN+_13") (pintype "input"))
      (node (ref "ERN1") (pin "6") (pinfunction "2_6") (pintype "passive"))
      (node (ref "U$2") (pin "RD+") (pinfunction "RD+_RD+") (pintype "bidirectional"))
    )
    (net (code "58") (name "Net-(ENC-TPIN-)") (class "Default")
      (node (ref "ENC") (pin "12") (pinfunction "TPIN-_12") (pintype "input"))
      (node (ref "ERN1") (pin "5") (pinfunction "2_5") (pintype "passive"))
      (node (ref "U$2") (pin "RD-") (pinfunction "RD-_RD-") (pintype "bidirectional"))
    )
    (net (code "59") (name "Net-(ENC-TPOUT+)") (class "Default")
      (node (ref "ENC") (pin "17") (pinfunction "TPOUT+_17") (pintype "output"))
      (node (ref "ERN1") (pin "1") (pinfunction "1_1") (pintype "passive"))
      (node (ref "U$2") (pin "TD+") (pinfunction "TD+_TD+") (pintype "bidirectional"))
    )
    (net (code "60") (name "Net-(ENC-TPOUT-)") (class "Default")
      (node (ref "ENC") (pin "16") (pinfunction "TPOUT-_16") (pintype "output"))
      (node (ref "ERN1") (pin "2") (pinfunction "1_2") (pintype "passive"))
      (node (ref "U$2") (pin "TD-") (pinfunction "TD-_TD-") (pintype "bidirectional"))
    )
    (net (code "61") (name "Net-(ENC-VCAP)") (class "Default")
      (node (ref "EC3") (pin "+") (pinfunction "+_+") (pintype "passive"))
      (node (ref "ENC") (pin "1") (pinfunction "VCAP_1") (pintype "power_in"))
    )
    (net (code "62") (name "Net-(ERN1A-2)") (class "Default")
      (node (ref "EC4") (pin "1") (pinfunction "1_1") (pintype "passive"))
      (node (ref "EL1") (pin "2") (pinfunction "2_2") (pintype "passive"))
      (node (ref "ERN1") (pin "7") (pinfunction "2_7") (pintype "passive"))
      (node (ref "ERN1") (pin "8") (pinfunction "2_8") (pintype "passive"))
      (node (ref "U$2") (pin "P4") (pinfunction "P4_P4") (pintype "bidirectional"))
    )
    (net (code "63") (name "Net-(ERN1C-1)") (class "Default")
      (node (ref "EC5") (pin "1") (pinfunction "1_1") (pintype "passive"))
      (node (ref "ERN1") (pin "3") (pinfunction "1_3") (pintype "passive"))
      (node (ref "ERN1") (pin "4") (pinfunction "1_4") (pintype "passive"))
      (node (ref "U$2") (pin "P5") (pinfunction "P5_P5") (pintype "bidirectional"))
    )
    (net (code "64") (name "Net-(IC1-A0)") (class "Default")
      (node (ref "IC1") (pin "15") (pinfunction "A0_15") (pintype "input"))
      (node (ref "MR3") (pin "1") (pinfunction "1_1") (pintype "passive"))
    )
    (net (code "65") (name "Net-(IIR1A-2)") (class "Default")
      (node (ref "IIR1") (pin "8") (pinfunction "2_8") (pintype "passive"))
      (node (ref "OK1") (pin "1") (pinfunction "A_1") (pintype "passive"))
    )
    (net (code "66") (name "Net-(IIR1B-1)") (class "Default")
      (node (ref "IIR1") (pin "2") (pinfunction "1_2") (pintype "passive"))
      (node (ref "XI1") (pin "3") (pinfunction "SK_3") (pintype "passive"))
    )
    (net (code "67") (name "Net-(IIR1B-2)") (class "Default")
      (node (ref "IIR1") (pin "7") (pinfunction "2_7") (pintype "passive"))
      (node (ref "OK1") (pin "3") (pinfunction "A_3") (pintype "passive"))
    )
    (net (code "68") (name "Net-(IIR1C-1)") (class "Default")
      (node (ref "IIR1") (pin "3") (pinfunction "1_3") (pintype "passive"))
      (node (ref "XI1") (pin "4") (pinfunction "SK_4") (pintype "passive"))
    )
    (net (code "69") (name "Net-(IIR1C-2)") (class "Default")
      (node (ref "IIR1") (pin "6") (pinfunction "2_6") (pintype "passive"))
      (node (ref "OK1") (pin "5") (pinfunction "A_5") (pintype "passive"))
    )
    (net (code "70") (name "Net-(IIR1D-1)") (class "Default")
      (node (ref "IIR1") (pin "4") (pinfunction "1_4") (pintype "passive"))
      (node (ref "XI1") (pin "5") (pinfunction "SK_5") (pintype "passive"))
    )
    (net (code "71") (name "Net-(IIR1D-2)") (class "Default")
      (node (ref "IIR1") (pin "5") (pinfunction "2_5") (pintype "passive"))
      (node (ref "OK1") (pin "7") (pinfunction "A_7") (pintype "passive"))
    )
    (net (code "72") (name "Net-(IIR2A-2)") (class "Default")
      (node (ref "IIR2") (pin "8") (pinfunction "2_8") (pintype "passive"))
      (node (ref "OK2") (pin "1") (pinfunction "A_1") (pintype "passive"))
    )
    (net (code "73") (name "Net-(IIR2B-1)") (class "Default")
      (node (ref "IIR2") (pin "2") (pinfunction "1_2") (pintype "passive"))
      (node (ref "XI2") (pin "3") (pinfunction "SK_3") (pintype "passive"))
    )
    (net (code "74") (name "Net-(IIR2B-2)") (class "Default")
      (node (ref "IIR2") (pin "7") (pinfunction "2_7") (pintype "passive"))
      (node (ref "OK2") (pin "3") (pinfunction "A_3") (pintype "passive"))
    )
    (net (code "75") (name "Net-(IIR2C-1)") (class "Default")
      (node (ref "IIR2") (pin "3") (pinfunction "1_3") (pintype "passive"))
      (node (ref "XI2") (pin "4") (pinfunction "SK_4") (pintype "passive"))
    )
    (net (code "76") (name "Net-(IIR2C-2)") (class "Default")
      (node (ref "IIR2") (pin "6") (pinfunction "2_6") (pintype "passive"))
      (node (ref "OK2") (pin "5") (pinfunction "A_5") (pintype "passive"))
    )
    (net (code "77") (name "Net-(IIR2D-1)") (class "Default")
      (node (ref "IIR2") (pin "4") (pinfunction "1_4") (pintype "passive"))
      (node (ref "XI2") (pin "5") (pinfunction "SK_5") (pintype "passive"))
    )
    (net (code "78") (name "Net-(IIR2D-2)") (class "Default")
      (node (ref "IIR2") (pin "5") (pinfunction "2_5") (pintype "passive"))
      (node (ref "OK2") (pin "7") (pinfunction "A_7") (pintype "passive"))
    )
    (net (code "79") (name "Net-(INDL-PadA)") (class "Default")
      (node (ref "INDL") (pin "A") (pinfunction "A_A") (pintype "passive"))
      (node (ref "R6") (pin "2") (pinfunction "2_2") (pintype "passive"))
    )
    (net (code "80") (name "Net-(IR3A-2)") (class "Default")
      (node (ref "IL1") (pin "C") (pinfunction "C_C") (pintype "passive"))
      (node (ref "IR3") (pin "8") (pinfunction "2_8") (pintype "passive"))
    )
    (net (code "81") (name "Net-(IR3B-2)") (class "Default")
      (node (ref "IL2") (pin "C") (pinfunction "C_C") (pintype "passive"))
      (node (ref "IR3") (pin "7") (pinfunction "2_7") (pintype "passive"))
    )
    (net (code "82") (name "Net-(IR3C-2)") (class "Default")
      (node (ref "IL3") (pin "C") (pinfunction "C_C") (pintype "passive"))
      (node (ref "IR3") (pin "6") (pinfunction "2_6") (pintype "passive"))
    )
    (net (code "83") (name "Net-(IR3D-2)") (class "Default")
      (node (ref "IL4") (pin "C") (pinfunction "C_C") (pintype "passive"))
      (node (ref "IR3") (pin "5") (pinfunction "2_5") (pintype "passive"))
    )
    (net (code "84") (name "Net-(IR4A-2)") (class "Default")
      (node (ref "IL5") (pin "C") (pinfunction "C_C") (pintype "passive"))
      (node (ref "IR4") (pin "8") (pinfunction "2_8") (pintype "passive"))
    )
    (net (code "85") (name "Net-(IR4B-2)") (class "Default")
      (node (ref "IL6") (pin "C") (pinfunction "C_C") (pintype "passive"))
      (node (ref "IR4") (pin "7") (pinfunction "2_7") (pintype "passive"))
    )
    (net (code "86") (name "Net-(IR4C-2)") (class "Default")
      (node (ref "IL7") (pin "C") (pinfunction "C_C") (pintype "passive"))
      (node (ref "IR4") (pin "6") (pinfunction "2_6") (pintype "passive"))
    )
    (net (code "87") (name "Net-(IR4D-2)") (class "Default")
      (node (ref "IL8") (pin "C") (pinfunction "C_C") (pintype "passive"))
      (node (ref "IR4") (pin "5") (pinfunction "2_5") (pintype "passive"))
    )
    (net (code "88") (name "Net-(MC-PB6(XTAL1{slash}TOSC1))") (class "Default")
      (node (ref "MC") (pin "7") (pinfunction "PB6(XTAL1/TOSC1)_7") (pintype "bidirectional"))
      (node (ref "Q1") (pin "1") (pinfunction "1_1") (pintype "passive"))
    )
    (net (code "89") (name "Net-(MC-PB7(XTAL2{slash}TOSC2))") (class "Default")
      (node (ref "MC") (pin "8") (pinfunction "PB7(XTAL2/TOSC2)_8") (pintype "bidirectional"))
      (node (ref "Q1") (pin "3") (pinfunction "3_3") (pintype "passive"))
    )
    (net (code "90") (name "Net-(OD1-PadC)") (class "Default")
      (node (ref "OD1") (pin "C") (pinfunction "C_C") (pintype "passive"))
      (node (ref "OMF") (pin "2") (pinfunction "2_2") (pintype "bidirectional"))
    )
    (net (code "91") (name "Net-(OK3A-A)") (class "Default")
      (node (ref "OK3") (pin "1") (pinfunction "A_1") (pintype "passive"))
      (node (ref "OR1") (pin "4") (pinfunction "1_4") (pintype "passive"))
    )
    (net (code "92") (name "Net-(OK3A-COL)") (class "Default")
      (node (ref "OK3") (pin "16") (pinfunction "COL_16") (pintype "passive"))
      (node (ref "OR3") (pin "1") (pinfunction "1_1") (pintype "passive"))
    )
    (net (code "93") (name "Net-(OK3B-A)") (class "Default")
      (node (ref "OK3") (pin "3") (pinfunction "A_3") (pintype "passive"))
      (node (ref "OR1") (pin "3") (pinfunction "1_3") (pintype "passive"))
    )
    (net (code "94") (name "Net-(OK3B-COL)") (class "Default")
      (node (ref "OK3") (pin "14") (pinfunction "COL_14") (pintype "passive"))
      (node (ref "OR3") (pin "2") (pinfunction "1_2") (pintype "passive"))
    )
    (net (code "95") (name "Net-(OK3C-A)") (class "Default")
      (node (ref "OK3") (pin "5") (pinfunction "A_5") (pintype "passive"))
      (node (ref "OR1") (pin "2") (pinfunction "1_2") (pintype "passive"))
    )
    (net (code "96") (name "Net-(OK3C-COL)") (class "Default")
      (node (ref "OK3") (pin "12") (pinfunction "COL_12") (pintype "passive"))
      (node (ref "OR3") (pin "3") (pinfunction "1_3") (pintype "passive"))
    )
    (net (code "97") (name "Net-(OK3D-A)") (class "Default")
      (node (ref "OK3") (pin "7") (pinfunction "A_7") (pintype "passive"))
      (node (ref "OR1") (pin "1") (pinfunction "1_1") (pintype "passive"))
    )
    (net (code "98") (name "Net-(OK3D-COL)") (class "Default")
      (node (ref "OK3") (pin "10") (pinfunction "COL_10") (pintype "passive"))
      (node (ref "OR3") (pin "4") (pinfunction "1_4") (pintype "passive"))
    )
    (net (code "99") (name "Net-(OK4A-A)") (class "Default")
      (node (ref "OK4") (pin "1") (pinfunction "A_1") (pintype "passive"))
      (node (ref "OR4") (pin "4") (pinfunction "1_4") (pintype "passive"))
    )
    (net (code "100") (name "Net-(OK4A-COL)") (class "Default")
      (node (ref "OK4") (pin "16") (pinfunction "COL_16") (pintype "passive"))
      (node (ref "OR5") (pin "1") (pinfunction "1_1") (pintype "passive"))
    )
    (net (code "101") (name "Net-(OK4B-A)") (class "Default")
      (node (ref "OK4") (pin "3") (pinfunction "A_3") (pintype "passive"))
      (node (ref "OR4") (pin "3") (pinfunction "1_3") (pintype "passive"))
    )
    (net (code "102") (name "Net-(OK4B-COL)") (class "Default")
      (node (ref "OK4") (pin "14") (pinfunction "COL_14") (pintype "passive"))
      (node (ref "OR5") (pin "2") (pinfunction "1_2") (pintype "passive"))
    )
    (net (code "103") (name "Net-(OK4C-A)") (class "Default")
      (node (ref "OK4") (pin "5") (pinfunction "A_5") (pintype "passive"))
      (node (ref "OR4") (pin "2") (pinfunction "1_2") (pintype "passive"))
    )
    (net (code "104") (name "Net-(OK4C-COL)") (class "Default")
      (node (ref "OK4") (pin "12") (pinfunction "COL_12") (pintype "passive"))
      (node (ref "OR5") (pin "3") (pinfunction "1_3") (pintype "passive"))
    )
    (net (code "105") (name "Net-(OK4D-A)") (class "Default")
      (node (ref "OK4") (pin "7") (pinfunction "A_7") (pintype "passive"))
      (node (ref "OR4") (pin "1") (pinfunction "1_1") (pintype "passive"))
    )
    (net (code "106") (name "Net-(OK4D-COL)") (class "Default")
      (node (ref "OK4") (pin "10") (pinfunction "COL_10") (pintype "passive"))
      (node (ref "OR5") (pin "4") (pinfunction "1_4") (pintype "passive"))
    )
    (net (code "107") (name "Net-(OL4-PadA)") (class "Default")
      (node (ref "OL4") (pin "A") (pinfunction "A_A") (pintype "passive"))
      (node (ref "OR7") (pin "1") (pinfunction "1_1") (pintype "passive"))
    )
    (net (code "108") (name "Net-(OL8-PadA)") (class "Default")
      (node (ref "OL8") (pin "A") (pinfunction "A_A") (pintype "passive"))
      (node (ref "OR8") (pin "1") (pinfunction "1_1") (pintype "passive"))
    )
    (net (code "109") (name "Net-(OR7B-1)") (class "Default")
      (node (ref "OL3") (pin "A") (pinfunction "A_A") (pintype "passive"))
      (node (ref "OR7") (pin "2") (pinfunction "1_2") (pintype "passive"))
    )
    (net (code "110") (name "Net-(OR7C-1)") (class "Default")
      (node (ref "OL2") (pin "A") (pinfunction "A_A") (pintype "passive"))
      (node (ref "OR7") (pin "3") (pinfunction "1_3") (pintype "passive"))
    )
    (net (code "111") (name "Net-(OR7D-1)") (class "Default")
      (node (ref "OL1") (pin "A") (pinfunction "A_A") (pintype "passive"))
      (node (ref "OR7") (pin "4") (pinfunction "1_4") (pintype "passive"))
    )
    (net (code "112") (name "Net-(OR8B-1)") (class "Default")
      (node (ref "OL7") (pin "A") (pinfunction "A_A") (pintype "passive"))
      (node (ref "OR8") (pin "2") (pinfunction "1_2") (pintype "passive"))
    )
    (net (code "113") (name "Net-(OR8C-1)") (class "Default")
      (node (ref "OL6") (pin "A") (pinfunction "A_A") (pintype "passive"))
      (node (ref "OR8") (pin "3") (pinfunction "1_3") (pintype "passive"))
    )
    (net (code "114") (name "Net-(OR8D-1)") (class "Default")
      (node (ref "OL5") (pin "A") (pinfunction "A_A") (pintype "passive"))
      (node (ref "OR8") (pin "4") (pinfunction "1_4") (pintype "passive"))
    )
    (net (code "115") (name "Net-(PD1-PadC)") (class "Default")
      (node (ref "PD1") (pin "C") (pinfunction "C_C") (pintype "passive"))
      (node (ref "PF1") (pin "1") (pinfunction "1_1") (pintype "passive"))
    )
    (net (code "116") (name "Net-(PIC33-OUT)") (class "Default")
      (node (ref "PCO") (pin "P$2") (pinfunction "P$2_P$2") (pintype "passive"))
      (node (ref "PD2") (pin "C") (pinfunction "C_C") (pintype "passive"))
      (node (ref "PIC33") (pin "2") (pinfunction "OUT_2") (pintype "output"))
    )
    (net (code "117") (name "Net-(PL-PadA)") (class "Default")
      (node (ref "PL") (pin "A") (pinfunction "A_A") (pintype "passive"))
      (node (ref "PR1") (pin "1") (pinfunction "1_1") (pintype "passive"))
    )
    (net (code "118") (name "Net-(U1-1C)") (class "Default")
      (node (ref "D1") (pin "2") (pinfunction "2_2") (pintype "bidirectional"))
      (node (ref "OF8") (pin "2") (pinfunction "2_2") (pintype "bidirectional"))
      (node (ref "U1") (pin "18") (pinfunction "1C_18") (pintype "output"))
    )
    (net (code "119") (name "Net-(U1-2C)") (class "Default")
      (node (ref "D1") (pin "1") (pinfunction "1_1") (pintype "bidirectional"))
      (node (ref "OF7") (pin "2") (pinfunction "2_2") (pintype "bidirectional"))
      (node (ref "U1") (pin "17") (pinfunction "2C_17") (pintype "output"))
    )
    (net (code "120") (name "Net-(U1-3C)") (class "Default")
      (node (ref "D2") (pin "2") (pinfunction "2_2") (pintype "bidirectional"))
      (node (ref "OF6") (pin "2") (pinfunction "2_2") (pintype "bidirectional"))
      (node (ref "U1") (pin "16") (pinfunction "3C_16") (pintype "output"))
    )
    (net (code "121") (name "Net-(U1-4C)") (class "Default")
      (node (ref "D2") (pin "1") (pinfunction "1_1") (pintype "bidirectional"))
      (node (ref "OF5") (pin "2") (pinfunction "2_2") (pintype "bidirectional"))
      (node (ref "U1") (pin "15") (pinfunction "4C_15") (pintype "output"))
    )
    (net (code "122") (name "Net-(U1-5C)") (class "Default")
      (node (ref "D3") (pin "2") (pinfunction "2_2") (pintype "bidirectional"))
      (node (ref "OF4") (pin "2") (pinfunction "2_2") (pintype "bidirectional"))
      (node (ref "U1") (pin "14") (pinfunction "5C_14") (pintype "output"))
    )
    (net (code "123") (name "Net-(U1-6C)") (class "Default")
      (node (ref "D3") (pin "1") (pinfunction "1_1") (pintype "bidirectional"))
      (node (ref "OF3") (pin "2") (pinfunction "2_2") (pintype "bidirectional"))
      (node (ref "U1") (pin "13") (pinfunction "6C_13") (pintype "output"))
    )
    (net (code "124") (name "Net-(U1-7C)") (class "Default")
      (node (ref "D4") (pin "2") (pinfunction "2_2") (pintype "bidirectional"))
      (node (ref "OF2") (pin "2") (pinfunction "2_2") (pintype "bidirectional"))
      (node (ref "U1") (pin "12") (pinfunction "7C_12") (pintype "output"))
    )
    (net (code "125") (name "Net-(U1-8C)") (class "Default")
      (node (ref "D4") (pin "1") (pinfunction "1_1") (pintype "bidirectional"))
      (node (ref "OF1") (pin "2") (pinfunction "2_2") (pintype "bidirectional"))
      (node (ref "U1") (pin "11") (pinfunction "8C_11") (pintype "output"))
    )
    (net (code "126") (name "Net-(XI1B-SK)") (class "Default")
      (node (ref "IIR1") (pin "1") (pinfunction "1_1") (pintype "passive"))
      (node (ref "XI1") (pin "2") (pinfunction "SK_2") (pintype "passive"))
    )
    (net (code "127") (name "Net-(XI2B-SK)") (class "Default")
      (node (ref "IIR2") (pin "1") (pinfunction "1_1") (pintype "passive"))
      (node (ref "XI2") (pin "2") (pinfunction "SK_2") (pintype "passive"))
    )
    (net (code "128") (name "Net-(XOA-SK)") (class "Default")
      (node (ref "OD1") (pin "A") (pinfunction "A_A") (pintype "passive"))
      (node (ref "XO") (pin "1") (pinfunction "SK_1") (pintype "passive"))
    )
    (net (code "129") (name "Net-(XOB-SK)") (class "Default")
      (node (ref "OF8") (pin "1") (pinfunction "1_1") (pintype "bidirectional"))
      (node (ref "XO") (pin "10") (pinfunction "SK_10") (pintype "passive"))
    )
    (net (code "130") (name "Net-(XOD-SK)") (class "Default")
      (node (ref "OF1") (pin "1") (pinfunction "1_1") (pintype "bidirectional"))
      (node (ref "XO") (pin "3") (pinfunction "SK_3") (pintype "passive"))
    )
    (net (code "131") (name "Net-(XOE-SK)") (class "Default")
      (node (ref "OF2") (pin "1") (pinfunction "1_1") (pintype "bidirectional"))
      (node (ref "XO") (pin "4") (pinfunction "SK_4") (pintype "passive"))
    )
    (net (code "132") (name "Net-(XOF-SK)") (class "Default")
      (node (ref "OF3") (pin "1") (pinfunction "1_1") (pintype "bidirectional"))
      (node (ref "XO") (pin "5") (pinfunction "SK_5") (pintype "passive"))
    )
    (net (code "133") (name "Net-(XOG-SK)") (class "Default")
      (node (ref "OF4") (pin "1") (pinfunction "1_1") (pintype "bidirectional"))
      (node (ref "XO") (pin "6") (pinfunction "SK_6") (pintype "passive"))
    )
    (net (code "134") (name "Net-(XOH-SK)") (class "Default")
      (node (ref "OF5") (pin "1") (pinfunction "1_1") (pintype "bidirectional"))
      (node (ref "XO") (pin "7") (pinfunction "SK_7") (pintype "passive"))
    )
    (net (code "135") (name "Net-(XOI-SK)") (class "Default")
      (node (ref "OF6") (pin "1") (pinfunction "1_1") (pintype "bidirectional"))
      (node (ref "XO") (pin "8") (pinfunction "SK_8") (pintype "passive"))
    )
    (net (code "136") (name "Net-(XOJ-SK)") (class "Default")
      (node (ref "OF7") (pin "1") (pinfunction "1_1") (pintype "bidirectional"))
      (node (ref "XO") (pin "9") (pinfunction "SK_9") (pintype "passive"))
    )
    (net (code "137") (name "OI1") (class "Default")
      (node (ref "OK3") (pin "15") (pinfunction "EMIT_15") (pintype "passive"))
      (node (ref "OR2") (pin "1") (pinfunction "1_1") (pintype "passive"))
      (node (ref "U1") (pin "8") (pinfunction "8B_8") (pintype "input"))
    )
    (net (code "138") (name "OI2") (class "Default")
      (node (ref "OK3") (pin "13") (pinfunction "EMIT_13") (pintype "passive"))
      (node (ref "OR2") (pin "2") (pinfunction "1_2") (pintype "passive"))
      (node (ref "U1") (pin "7") (pinfunction "7B_7") (pintype "input"))
    )
    (net (code "139") (name "OI3") (class "Default")
      (node (ref "OK3") (pin "11") (pinfunction "EMIT_11") (pintype "passive"))
      (node (ref "OR2") (pin "3") (pinfunction "1_3") (pintype "passive"))
      (node (ref "U1") (pin "6") (pinfunction "6B_6") (pintype "input"))
    )
    (net (code "140") (name "OI4") (class "Default")
      (node (ref "OK3") (pin "9") (pinfunction "EMIT_9") (pintype "passive"))
      (node (ref "OR2") (pin "4") (pinfunction "1_4") (pintype "passive"))
      (node (ref "U1") (pin "5") (pinfunction "5B_5") (pintype "input"))
    )
    (net (code "141") (name "RAW_IV") (class "Default")
      (node (ref "GPIO") (pin "1") (pinfunction "S_1") (pintype "passive"))
      (node (ref "PC1") (pin "+") (pinfunction "+_+") (pintype "passive"))
      (node (ref "PF1") (pin "2") (pinfunction "2_2") (pintype "passive"))
      (node (ref "PIC33") (pin "1") (pinfunction "VIN_1") (pintype "input"))
    )
    (net (code "142") (name "RESET") (class "Default")
      (node (ref "BL") (pin "5") (pinfunction "S_5") (pintype "passive"))
      (node (ref "C2") (pin "1") (pinfunction "1_1") (pintype "passive"))
      (node (ref "MC") (pin "29") (pinfunction "PC6(/RESET)_29") (pintype "bidirectional"))
      (node (ref "R2") (pin "1") (pinfunction "1_1") (pintype "passive"))
      (node (ref "SR") (pin "1") (pinfunction "P_1") (pintype "passive"))
    )
    (net (code "143") (name "RXI") (class "Default")
      (node (ref "MC") (pin "30") (pinfunction "PD0(RXD)_30") (pintype "bidirectional"))
      (node (ref "PP") (pin "4") (pinfunction "S_4") (pintype "passive"))
    )
    (net (code "144") (name "TXO") (class "Default")
      (node (ref "MC") (pin "31") (pinfunction "PD1(TXD)_31") (pintype "bidirectional"))
      (node (ref "PP") (pin "3") (pinfunction "S_3") (pintype "passive"))
    )
    (net (code "145") (name "VDDO") (class "Default")
      (node (ref "D1") (pin "3") (pinfunction "3_3") (pintype "bidirectional"))
      (node (ref "D2") (pin "3") (pinfunction "3_3") (pintype "bidirectional"))
      (node (ref "D3") (pin "3") (pinfunction "3_3") (pintype "bidirectional"))
      (node (ref "D4") (pin "3") (pinfunction "3_3") (pintype "bidirectional"))
      (node (ref "EC6") (pin "+") (pinfunction "+_+") (pintype "passive"))
      (node (ref "OD2") (pin "C") (pinfunction "C_C") (pintype "passive"))
      (node (ref "OMF") (pin "1") (pinfunction "1_1") (pintype "bidirectional"))
      (node (ref "OR3") (pin "5") (pinfunction "2_5") (pintype "passive"))
      (node (ref "OR3") (pin "6") (pinfunction "2_6") (pintype "passive"))
      (node (ref "OR3") (pin "7") (pinfunction "2_7") (pintype "passive"))
      (node (ref "OR3") (pin "8") (pinfunction "2_8") (pintype "passive"))
      (node (ref "OR5") (pin "5") (pinfunction "2_5") (pintype "passive"))
      (node (ref "OR5") (pin "6") (pinfunction "2_6") (pintype "passive"))
      (node (ref "OR5") (pin "7") (pinfunction "2_7") (pintype "passive"))
      (node (ref "OR5") (pin "8") (pinfunction "2_8") (pintype "passive"))
      (node (ref "U1") (pin "10") (pinfunction "COM_10") (pintype "output"))
    )
    (net (code "146") (name "VIN") (class "Default")
      (node (ref "PD1") (pin "A") (pinfunction "A_A") (pintype "passive"))
      (node (ref "PJ1") (pin "VIN0") (pinfunction "PWR_VIN0") (pintype "bidirectional"))
      (node (ref "XV") (pin "2") (pinfunction "SK_2") (pintype "passive"))
    )
    (net (code "147") (name "WFGPIO0") (class "Default")
      (node (ref "GPIO") (pin "13") (pinfunction "S_13") (pintype "passive"))
      (node (ref "WIFI") (pin "GPIO0") (pinfunction "GPIO0_GPIO0") (pintype "bidirectional"))
    )
    (net (code "148") (name "WFGPIO2") (class "Default")
      (node (ref "GPIO") (pin "14") (pinfunction "S_14") (pintype "passive"))
      (node (ref "WIFI") (pin "GPIO2") (pinfunction "GPIO2_GPIO2") (pintype "bidirectional"))
    )
    (net (code "149") (name "unconnected-(ENC-CLKOUT-Pad3)") (class "Default")
      (node (ref "ENC") (pin "3") (pinfunction "CLKOUT_3") (pintype "output"))
    )
    (net (code "150") (name "unconnected-(ENC-WOL-Pad5)") (class "Default")
      (node (ref "ENC") (pin "5") (pinfunction "WOL_5") (pintype "output"))
    )
    (net (code "151") (name "unconnected-(IC1-INTA-Pad20)") (class "Default")
      (node (ref "IC1") (pin "20") (pinfunction "INTA_20") (pintype "output"))
    )
    (net (code "152") (name "unconnected-(PJ1-GND-PadP$4)") (class "Default")
      (node (ref "PJ1") (pin "P$4") (pinfunction "GND_P$4") (pintype "bidirectional"))
    )
    (net (code "153") (name "unconnected-(U$2-PadNC)") (class "Default")
      (node (ref "U$2") (pin "NC") (pinfunction "NC_NC") (pintype "bidirectional"))
    )
    (net (code "154") (name "unconnected-(WIFI-PadRST)") (class "Default")
      (node (ref "WIFI") (pin "RST") (pinfunction "RST_RST") (pintype "bidirectional"))
    )
  )
)
